# Rear_Lamp.net
KiCad netlist of a schematic drawn in EAGLE
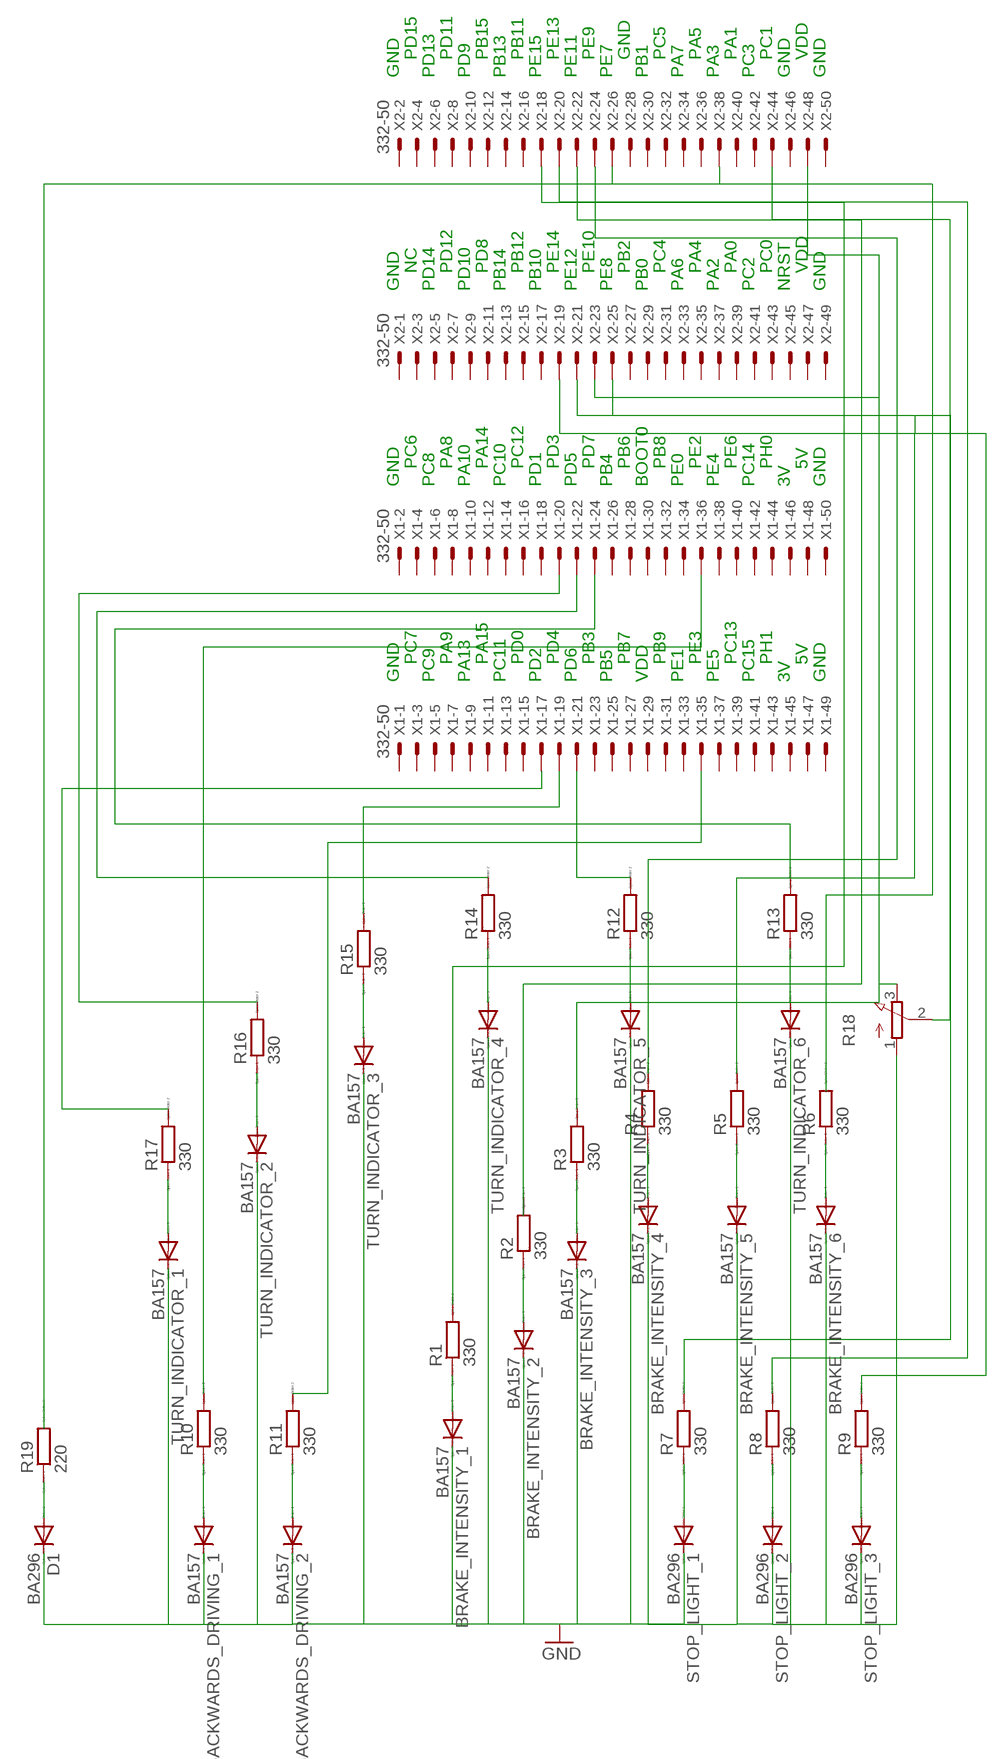
[diagram p0: schematic, sheet 1]

(export (version "E")
  (design (tool "Eeschema 10.0.6"))
  (components
    (comp (ref "BACKWARDS_DRIVING_1")
      (value "BA157")
      (footprint "eagle-import:P1-10")
      (libsource (lib "eagle-import") (part "BA157"))
    )
    (comp (ref "BACKWARDS_DRIVING_2")
      (value "BA157")
      (footprint "eagle-import:P1-10")
      (libsource (lib "eagle-import") (part "BA157"))
    )
    (comp (ref "BRAKE_INTENSITY_1")
      (value "BA157")
      (footprint "eagle-import:P1-10")
      (libsource (lib "eagle-import") (part "BA157"))
    )
    (comp (ref "BRAKE_INTENSITY_2")
      (value "BA157")
      (footprint "eagle-import:P1-10")
      (libsource (lib "eagle-import") (part "BA157"))
    )
    (comp (ref "BRAKE_INTENSITY_3")
      (value "BA157")
      (footprint "eagle-import:P1-10")
      (libsource (lib "eagle-import") (part "BA157"))
    )
    (comp (ref "BRAKE_INTENSITY_4")
      (value "BA157")
      (footprint "eagle-import:P1-10")
      (libsource (lib "eagle-import") (part "BA157"))
    )
    (comp (ref "BRAKE_INTENSITY_5")
      (value "BA157")
      (footprint "eagle-import:P1-10")
      (libsource (lib "eagle-import") (part "BA157"))
    )
    (comp (ref "BRAKE_INTENSITY_6")
      (value "BA157")
      (footprint "eagle-import:P1-10")
      (libsource (lib "eagle-import") (part "BA157"))
    )
    (comp (ref "D1")
      (value "BA296")
      (footprint "eagle-import:P2-15")
      (libsource (lib "eagle-import") (part "BA296"))
    )
    (comp (ref "R1")
      (value "330")
      (footprint "eagle-import:0204_7")
      (libsource (lib "eagle-import") (part "R0204/7"))
    )
    (comp (ref "R2")
      (value "330")
      (footprint "eagle-import:0204_7")
      (libsource (lib "eagle-import") (part "R0204/7"))
    )
    (comp (ref "R3")
      (value "330")
      (footprint "eagle-import:0204_7")
      (libsource (lib "eagle-import") (part "R0204/7"))
    )
    (comp (ref "R4")
      (value "330")
      (footprint "eagle-import:0204_7")
      (libsource (lib "eagle-import") (part "R0204/7"))
    )
    (comp (ref "R5")
      (value "330")
      (footprint "eagle-import:0204_7")
      (libsource (lib "eagle-import") (part "R0204/7"))
    )
    (comp (ref "R6")
      (value "330")
      (footprint "eagle-import:0204_7")
      (libsource (lib "eagle-import") (part "R0204/7"))
    )
    (comp (ref "R7")
      (value "330")
      (footprint "eagle-import:0204_7")
      (libsource (lib "eagle-import") (part "R0204/7"))
    )
    (comp (ref "R8")
      (value "330")
      (footprint "eagle-import:0204_7")
      (libsource (lib "eagle-import") (part "R0204/7"))
    )
    (comp (ref "R9")
      (value "330")
      (footprint "eagle-import:0204_7")
      (libsource (lib "eagle-import") (part "R0204/7"))
    )
    (comp (ref "R10")
      (value "330")
      (footprint "eagle-import:0204_7")
      (libsource (lib "eagle-import") (part "R0204/7"))
    )
    (comp (ref "R11")
      (value "330")
      (footprint "eagle-import:0204_7")
      (libsource (lib "eagle-import") (part "R0204/7"))
    )
    (comp (ref "R12")
      (value "330")
      (footprint "eagle-import:0204_7")
      (libsource (lib "eagle-import") (part "R0204/7"))
    )
    (comp (ref "R13")
      (value "330")
      (footprint "eagle-import:0204_7")
      (libsource (lib "eagle-import") (part "R0204/7"))
    )
    (comp (ref "R14")
      (value "330")
      (footprint "eagle-import:0204_7")
      (libsource (lib "eagle-import") (part "R0204/7"))
    )
    (comp (ref "R15")
      (value "330")
      (footprint "eagle-import:0204_7")
      (libsource (lib "eagle-import") (part "R0204/7"))
    )
    (comp (ref "R16")
      (value "330")
      (footprint "eagle-import:0204_7")
      (libsource (lib "eagle-import") (part "R0204/7"))
    )
    (comp (ref "R17")
      (value "330")
      (footprint "eagle-import:0204_7")
      (libsource (lib "eagle-import") (part "R0204/7"))
    )
    (comp (ref "R18")
      (value "3RP/1610N")
      (footprint "eagle-import:3RP_1610N")
      (libsource (lib "eagle-import") (part "3RP/1610N"))
    )
    (comp (ref "R19")
      (value "220")
      (footprint "eagle-import:0204_7")
      (libsource (lib "eagle-import") (part "R0204/7"))
    )
    (comp (ref "STOP_LIGHT_1")
      (value "BA296")
      (footprint "eagle-import:P2-15")
      (libsource (lib "eagle-import") (part "BA296"))
    )
    (comp (ref "STOP_LIGHT_2")
      (value "BA296")
      (footprint "eagle-import:P2-15")
      (libsource (lib "eagle-import") (part "BA296"))
    )
    (comp (ref "STOP_LIGHT_3")
      (value "BA296")
      (footprint "eagle-import:P2-15")
      (libsource (lib "eagle-import") (part "BA296"))
    )
    (comp (ref "TURN_INDICATOR_1")
      (value "BA157")
      (footprint "eagle-import:P1-10")
      (libsource (lib "eagle-import") (part "BA157"))
    )
    (comp (ref "TURN_INDICATOR_2")
      (value "BA157")
      (footprint "eagle-import:P1-10")
      (libsource (lib "eagle-import") (part "BA157"))
    )
    (comp (ref "TURN_INDICATOR_3")
      (value "BA157")
      (footprint "eagle-import:P1-10")
      (libsource (lib "eagle-import") (part "BA157"))
    )
    (comp (ref "TURN_INDICATOR_4")
      (value "BA157")
      (footprint "eagle-import:P1-10")
      (libsource (lib "eagle-import") (part "BA157"))
    )
    (comp (ref "TURN_INDICATOR_5")
      (value "BA157")
      (footprint "eagle-import:P1-10")
      (libsource (lib "eagle-import") (part "BA157"))
    )
    (comp (ref "TURN_INDICATOR_6")
      (value "BA157")
      (footprint "eagle-import:P1-10")
      (libsource (lib "eagle-import") (part "BA157"))
    )
    (comp (ref "X1")
      (value "332-50")
      (footprint "eagle-import:332-50")
      (libsource (lib "eagle-import") (part "332-50"))
    )
    (comp (ref "X2")
      (value "332-50")
      (footprint "eagle-import:332-50")
      (libsource (lib "eagle-import") (part "332-50"))
    )
  )
  (nets
    (net (code "2") (name "Net-(BACKWARDS_DRIVING_1-PadA)") (class "Default")
      (node (ref "BACKWARDS_DRIVING_1") (pin "A") (pinfunction "A_A") (pintype "passive"))
      (node (ref "R10") (pin "1") (pinfunction "1_1") (pintype "passive"))
    )
    (net (code "3") (name "Net-(BACKWARDS_DRIVING_2-PadA)") (class "Default")
      (node (ref "BACKWARDS_DRIVING_2") (pin "A") (pinfunction "A_A") (pintype "passive"))
      (node (ref "R11") (pin "1") (pinfunction "1_1") (pintype "passive"))
    )
    (net (code "4") (name "Net-(BRAKE_INTENSITY_1-PadA)") (class "Default")
      (node (ref "BRAKE_INTENSITY_1") (pin "A") (pinfunction "A_A") (pintype "passive"))
      (node (ref "R1") (pin "1") (pinfunction "1_1") (pintype "passive"))
    )
    (net (code "5") (name "Net-(BRAKE_INTENSITY_2-PadA)") (class "Default")
      (node (ref "BRAKE_INTENSITY_2") (pin "A") (pinfunction "A_A") (pintype "passive"))
      (node (ref "R2") (pin "1") (pinfunction "1_1") (pintype "passive"))
    )
    (net (code "6") (name "Net-(BRAKE_INTENSITY_3-PadA)") (class "Default")
      (node (ref "BRAKE_INTENSITY_3") (pin "A") (pinfunction "A_A") (pintype "passive"))
      (node (ref "R3") (pin "1") (pinfunction "1_1") (pintype "passive"))
    )
    (net (code "7") (name "Net-(BRAKE_INTENSITY_4-PadA)") (class "Default")
      (node (ref "BRAKE_INTENSITY_4") (pin "A") (pinfunction "A_A") (pintype "passive"))
      (node (ref "R4") (pin "1") (pinfunction "1_1") (pintype "passive"))
    )
    (net (code "8") (name "Net-(BRAKE_INTENSITY_5-PadA)") (class "Default")
      (node (ref "BRAKE_INTENSITY_5") (pin "A") (pinfunction "A_A") (pintype "passive"))
      (node (ref "R5") (pin "1") (pinfunction "1_1") (pintype "passive"))
    )
    (net (code "9") (name "Net-(BRAKE_INTENSITY_6-PadA)") (class "Default")
      (node (ref "BRAKE_INTENSITY_6") (pin "A") (pinfunction "A_A") (pintype "passive"))
      (node (ref "R6") (pin "1") (pinfunction "1_1") (pintype "passive"))
    )
    (net (code "10") (name "Net-(D1-PadA)") (class "Default")
      (node (ref "D1") (pin "A") (pinfunction "A_A") (pintype "passive"))
      (node (ref "R19") (pin "1") (pinfunction "1_1") (pintype "passive"))
    )
    (net (code "11") (name "Net-(R7-Pad1)") (class "Default")
      (node (ref "R7") (pin "1") (pinfunction "1_1") (pintype "passive"))
      (node (ref "STOP_LIGHT_1") (pin "A") (pinfunction "A_A") (pintype "passive"))
    )
    (net (code "12") (name "Net-(R8-Pad1)") (class "Default")
      (node (ref "R8") (pin "1") (pinfunction "1_1") (pintype "passive"))
      (node (ref "STOP_LIGHT_2") (pin "A") (pinfunction "A_A") (pintype "passive"))
    )
    (net (code "13") (name "Net-(R9-Pad1)") (class "Default")
      (node (ref "R9") (pin "1") (pinfunction "1_1") (pintype "passive"))
      (node (ref "STOP_LIGHT_3") (pin "A") (pinfunction "A_A") (pintype "passive"))
    )
    (net (code "14") (name "Net-(R12-Pad1)") (class "Default")
      (node (ref "R12") (pin "1") (pinfunction "1_1") (pintype "passive"))
      (node (ref "TURN_INDICATOR_5") (pin "A") (pinfunction "A_A") (pintype "passive"))
    )
    (net (code "15") (name "Net-(R13-Pad1)") (class "Default")
      (node (ref "R13") (pin "1") (pinfunction "1_1") (pintype "passive"))
      (node (ref "TURN_INDICATOR_6") (pin "A") (pinfunction "A_A") (pintype "passive"))
    )
    (net (code "16") (name "Net-(R14-Pad1)") (class "Default")
      (node (ref "R14") (pin "1") (pinfunction "1_1") (pintype "passive"))
      (node (ref "TURN_INDICATOR_4") (pin "A") (pinfunction "A_A") (pintype "passive"))
    )
    (net (code "17") (name "Net-(R15-Pad1)") (class "Default")
      (node (ref "R15") (pin "1") (pinfunction "1_1") (pintype "passive"))
      (node (ref "TURN_INDICATOR_3") (pin "A") (pinfunction "A_A") (pintype "passive"))
    )
    (net (code "18") (name "Net-(R16-Pad1)") (class "Default")
      (node (ref "R16") (pin "1") (pinfunction "1_1") (pintype "passive"))
      (node (ref "TURN_INDICATOR_2") (pin "A") (pinfunction "A_A") (pintype "passive"))
    )
    (net (code "19") (name "Net-(R17-Pad1)") (class "Default")
      (node (ref "R17") (pin "1") (pinfunction "1_1") (pintype "passive"))
      (node (ref "TURN_INDICATOR_1") (pin "A") (pinfunction "A_A") (pintype "passive"))
    )
    (net (code "20") (name "Net-(R18-A)") (class "Default")
      (node (ref "BACKWARDS_DRIVING_1") (pin "C") (pinfunction "C_C") (pintype "passive"))
      (node (ref "BACKWARDS_DRIVING_2") (pin "C") (pinfunction "C_C") (pintype "passive"))
      (node (ref "BRAKE_INTENSITY_1") (pin "C") (pinfunction "C_C") (pintype "passive"))
      (node (ref "BRAKE_INTENSITY_2") (pin "C") (pinfunction "C_C") (pintype "passive"))
      (node (ref "BRAKE_INTENSITY_3") (pin "C") (pinfunction "C_C") (pintype "passive"))
      (node (ref "BRAKE_INTENSITY_4") (pin "C") (pinfunction "C_C") (pintype "passive"))
      (node (ref "BRAKE_INTENSITY_5") (pin "C") (pinfunction "C_C") (pintype "passive"))
      (node (ref "BRAKE_INTENSITY_6") (pin "C") (pinfunction "C_C") (pintype "passive"))
      (node (ref "D1") (pin "C") (pinfunction "C_C") (pintype "passive"))
      (node (ref "R18") (pin "1") (pinfunction "A_1") (pintype "passive"))
      (node (ref "STOP_LIGHT_1") (pin "C") (pinfunction "C_C") (pintype "passive"))
      (node (ref "STOP_LIGHT_2") (pin "C") (pinfunction "C_C") (pintype "passive"))
      (node (ref "STOP_LIGHT_3") (pin "C") (pinfunction "C_C") (pintype "passive"))
      (node (ref "TURN_INDICATOR_1") (pin "C") (pinfunction "C_C") (pintype "passive"))
      (node (ref "TURN_INDICATOR_2") (pin "C") (pinfunction "C_C") (pintype "passive"))
      (node (ref "TURN_INDICATOR_3") (pin "C") (pinfunction "C_C") (pintype "passive"))
      (node (ref "TURN_INDICATOR_4") (pin "C") (pinfunction "C_C") (pintype "passive"))
      (node (ref "TURN_INDICATOR_5") (pin "C") (pinfunction "C_C") (pintype "passive"))
      (node (ref "TURN_INDICATOR_6") (pin "C") (pinfunction "C_C") (pintype "passive"))
    )
    (net (code "21") (name "Net-(R18-E)") (class "Default")
      (node (ref "R18") (pin "3") (pinfunction "E_3") (pintype "passive"))
      (node (ref "X2") (pin "48") (pinfunction "S_48") (pintype "passive"))
    )
    (net (code "22") (name "Net-(R18-S)") (class "Default")
      (node (ref "R18") (pin "2") (pinfunction "S_2") (pintype "passive"))
      (node (ref "X2") (pin "44") (pinfunction "S_44") (pintype "passive"))
    )
    (net (code "23") (name "Net-(X1AC-S)") (class "Default")
      (node (ref "R11") (pin "2") (pinfunction "2_2") (pintype "passive"))
      (node (ref "X1") (pin "35") (pinfunction "S_35") (pintype "passive"))
    )
    (net (code "24") (name "Net-(X1AD-S)") (class "Default")
      (node (ref "R10") (pin "2") (pinfunction "2_2") (pintype "passive"))
      (node (ref "X1") (pin "36") (pinfunction "S_36") (pintype "passive"))
    )
    (net (code "25") (name "Net-(X1I-S)") (class "Default")
      (node (ref "R17") (pin "2") (pinfunction "2_2") (pintype "passive"))
      (node (ref "X1") (pin "17") (pinfunction "S_17") (pintype "passive"))
    )
    (net (code "26") (name "Net-(X1K-S)") (class "Default")
      (node (ref "R15") (pin "2") (pinfunction "2_2") (pintype "passive"))
      (node (ref "X1") (pin "19") (pinfunction "S_19") (pintype "passive"))
    )
    (net (code "27") (name "Net-(X1M-S)") (class "Default")
      (node (ref "R16") (pin "2") (pinfunction "2_2") (pintype "passive"))
      (node (ref "X1") (pin "20") (pinfunction "S_20") (pintype "passive"))
    )
    (net (code "28") (name "Net-(X1N-S)") (class "Default")
      (node (ref "R12") (pin "2") (pinfunction "2_2") (pintype "passive"))
      (node (ref "X1") (pin "21") (pinfunction "S_21") (pintype "passive"))
    )
    (net (code "29") (name "Net-(X1O-S)") (class "Default")
      (node (ref "R14") (pin "2") (pinfunction "2_2") (pintype "passive"))
      (node (ref "X1") (pin "22") (pinfunction "S_22") (pintype "passive"))
    )
    (net (code "30") (name "Net-(X1Q-S)") (class "Default")
      (node (ref "R13") (pin "2") (pinfunction "2_2") (pintype "passive"))
      (node (ref "X1") (pin "24") (pinfunction "S_24") (pintype "passive"))
    )
    (net (code "31") (name "Net-(X2J-S)") (class "Default")
      (node (ref "R1") (pin "2") (pinfunction "2_2") (pintype "passive"))
      (node (ref "X2") (pin "18") (pinfunction "S_18") (pintype "passive"))
    )
    (net (code "32") (name "Net-(X2K-S)") (class "Default")
      (node (ref "R9") (pin "2") (pinfunction "2_2") (pintype "passive"))
      (node (ref "X2") (pin "19") (pinfunction "S_19") (pintype "passive"))
    )
    (net (code "33") (name "Net-(X2M-S)") (class "Default")
      (node (ref "R8") (pin "2") (pinfunction "2_2") (pintype "passive"))
      (node (ref "X2") (pin "20") (pinfunction "S_20") (pintype "passive"))
    )
    (net (code "34") (name "Net-(X2N-S)") (class "Default")
      (node (ref "R7") (pin "2") (pinfunction "2_2") (pintype "passive"))
      (node (ref "X2") (pin "21") (pinfunction "S_21") (pintype "passive"))
    )
    (net (code "35") (name "Net-(X2P-S)") (class "Default")
      (node (ref "R3") (pin "2") (pinfunction "2_2") (pintype "passive"))
      (node (ref "X2") (pin "23") (pinfunction "S_23") (pintype "passive"))
    )
    (net (code "36") (name "Net-(X2Q-S)") (class "Default")
      (node (ref "R4") (pin "2") (pinfunction "2_2") (pintype "passive"))
      (node (ref "X2") (pin "24") (pinfunction "S_24") (pintype "passive"))
    )
    (net (code "37") (name "Net-(X2R-S)") (class "Default")
      (node (ref "R5") (pin "2") (pinfunction "2_2") (pintype "passive"))
      (node (ref "X2") (pin "25") (pinfunction "S_25") (pintype "passive"))
    )
    (net (code "38") (name "unconnected-(R2-Pad2)") (class "Default")
      (node (ref "R2") (pin "2") (pinfunction "2_2") (pintype "passive"))
    )
    (net (code "39") (name "unconnected-(R6-Pad2)") (class "Default")
      (node (ref "R6") (pin "2") (pinfunction "2_2") (pintype "passive"))
    )
    (net (code "40") (name "unconnected-(R19-Pad2)") (class "Default")
      (node (ref "R19") (pin "2") (pinfunction "2_2") (pintype "passive"))
    )
    (net (code "41") (name "unconnected-(X1A-S-Pad1)") (class "Default")
      (node (ref "X1") (pin "1") (pinfunction "S_1") (pintype "passive"))
    )
    (net (code "42") (name "unconnected-(X1AA-S-Pad33)") (class "Default")
      (node (ref "X1") (pin "33") (pinfunction "S_33") (pintype "passive"))
    )
    (net (code "43") (name "unconnected-(X1AB-S-Pad34)") (class "Default")
      (node (ref "X1") (pin "34") (pinfunction "S_34") (pintype "passive"))
    )
    (net (code "44") (name "unconnected-(X1AE-S-Pad37)") (class "Default")
      (node (ref "X1") (pin "37") (pinfunction "S_37") (pintype "passive"))
    )
    (net (code "45") (name "unconnected-(X1AF-S-Pad38)") (class "Default")
      (node (ref "X1") (pin "38") (pinfunction "S_38") (pintype "passive"))
    )
    (net (code "46") (name "unconnected-(X1AG-S-Pad39)") (class "Default")
      (node (ref "X1") (pin "39") (pinfunction "S_39") (pintype "passive"))
    )
    (net (code "47") (name "unconnected-(X1AH-S-Pad4)") (class "Default")
      (node (ref "X1") (pin "4") (pinfunction "S_4") (pintype "passive"))
    )
    (net (code "48") (name "unconnected-(X1AI-S-Pad40)") (class "Default")
      (node (ref "X1") (pin "40") (pinfunction "S_40") (pintype "passive"))
    )
    (net (code "49") (name "unconnected-(X1AJ-S-Pad41)") (class "Default")
      (node (ref "X1") (pin "41") (pinfunction "S_41") (pintype "passive"))
    )
    (net (code "50") (name "unconnected-(X1AK-S-Pad42)") (class "Default")
      (node (ref "X1") (pin "42") (pinfunction "S_42") (pintype "passive"))
    )
    (net (code "51") (name "unconnected-(X1AL-S-Pad43)") (class "Default")
      (node (ref "X1") (pin "43") (pinfunction "S_43") (pintype "passive"))
    )
    (net (code "52") (name "unconnected-(X1AM-S-Pad44)") (class "Default")
      (node (ref "X1") (pin "44") (pinfunction "S_44") (pintype "passive"))
    )
    (net (code "53") (name "unconnected-(X1AN-S-Pad45)") (class "Default")
      (node (ref "X1") (pin "45") (pinfunction "S_45") (pintype "passive"))
    )
    (net (code "54") (name "unconnected-(X1AO-S-Pad46)") (class "Default")
      (node (ref "X1") (pin "46") (pinfunction "S_46") (pintype "passive"))
    )
    (net (code "55") (name "unconnected-(X1AP-S-Pad47)") (class "Default")
      (node (ref "X1") (pin "47") (pinfunction "S_47") (pintype "passive"))
    )
    (net (code "56") (name "unconnected-(X1AQ-S-Pad48)") (class "Default")
      (node (ref "X1") (pin "48") (pinfunction "S_48") (pintype "passive"))
    )
    (net (code "57") (name "unconnected-(X1AR-S-Pad49)") (class "Default")
      (node (ref "X1") (pin "49") (pinfunction "S_49") (pintype "passive"))
    )
    (net (code "58") (name "unconnected-(X1AS-S-Pad5)") (class "Default")
      (node (ref "X1") (pin "5") (pinfunction "S_5") (pintype "passive"))
    )
    (net (code "59") (name "unconnected-(X1AT-S-Pad50)") (class "Default")
      (node (ref "X1") (pin "50") (pinfunction "S_50") (pintype "passive"))
    )
    (net (code "60") (name "unconnected-(X1AU-S-Pad6)") (class "Default")
      (node (ref "X1") (pin "6") (pinfunction "S_6") (pintype "passive"))
    )
    (net (code "61") (name "unconnected-(X1AV-S-Pad7)") (class "Default")
      (node (ref "X1") (pin "7") (pinfunction "S_7") (pintype "passive"))
    )
    (net (code "62") (name "unconnected-(X1AW-S-Pad8)") (class "Default")
      (node (ref "X1") (pin "8") (pinfunction "S_8") (pintype "passive"))
    )
    (net (code "63") (name "unconnected-(X1AX-S-Pad9)") (class "Default")
      (node (ref "X1") (pin "9") (pinfunction "S_9") (pintype "passive"))
    )
    (net (code "64") (name "unconnected-(X1B-S-Pad10)") (class "Default")
      (node (ref "X1") (pin "10") (pinfunction "S_10") (pintype "passive"))
    )
    (net (code "65") (name "unconnected-(X1C-S-Pad11)") (class "Default")
      (node (ref "X1") (pin "11") (pinfunction "S_11") (pintype "passive"))
    )
    (net (code "66") (name "unconnected-(X1D-S-Pad12)") (class "Default")
      (node (ref "X1") (pin "12") (pinfunction "S_12") (pintype "passive"))
    )
    (net (code "67") (name "unconnected-(X1E-S-Pad13)") (class "Default")
      (node (ref "X1") (pin "13") (pinfunction "S_13") (pintype "passive"))
    )
    (net (code "68") (name "unconnected-(X1F-S-Pad14)") (class "Default")
      (node (ref "X1") (pin "14") (pinfunction "S_14") (pintype "passive"))
    )
    (net (code "69") (name "unconnected-(X1G-S-Pad15)") (class "Default")
      (node (ref "X1") (pin "15") (pinfunction "S_15") (pintype "passive"))
    )
    (net (code "70") (name "unconnected-(X1H-S-Pad16)") (class "Default")
      (node (ref "X1") (pin "16") (pinfunction "S_16") (pintype "passive"))
    )
    (net (code "71") (name "unconnected-(X1J-S-Pad18)") (class "Default")
      (node (ref "X1") (pin "18") (pinfunction "S_18") (pintype "passive"))
    )
    (net (code "72") (name "unconnected-(X1L-S-Pad2)") (class "Default")
      (node (ref "X1") (pin "2") (pinfunction "S_2") (pintype "passive"))
    )
    (net (code "73") (name "unconnected-(X1P-S-Pad23)") (class "Default")
      (node (ref "X1") (pin "23") (pinfunction "S_23") (pintype "passive"))
    )
    (net (code "74") (name "unconnected-(X1R-S-Pad25)") (class "Default")
      (node (ref "X1") (pin "25") (pinfunction "S_25") (pintype "passive"))
    )
    (net (code "75") (name "unconnected-(X1S-S-Pad26)") (class "Default")
      (node (ref "X1") (pin "26") (pinfunction "S_26") (pintype "passive"))
    )
    (net (code "76") (name "unconnected-(X1T-S-Pad27)") (class "Default")
      (node (ref "X1") (pin "27") (pinfunction "S_27") (pintype "passive"))
    )
    (net (code "77") (name "unconnected-(X1U-S-Pad28)") (class "Default")
      (node (ref "X1") (pin "28") (pinfunction "S_28") (pintype "passive"))
    )
    (net (code "78") (name "unconnected-(X1V-S-Pad29)") (class "Default")
      (node (ref "X1") (pin "29") (pinfunction "S_29") (pintype "passive"))
    )
    (net (code "79") (name "unconnected-(X1W-S-Pad3)") (class "Default")
      (node (ref "X1") (pin "3") (pinfunction "S_3") (pintype "passive"))
    )
    (net (code "80") (name "unconnected-(X1X-S-Pad30)") (class "Default")
      (node (ref "X1") (pin "30") (pinfunction "S_30") (pintype "passive"))
    )
    (net (code "81") (name "unconnected-(X1Y-S-Pad31)") (class "Default")
      (node (ref "X1") (pin "31") (pinfunction "S_31") (pintype "passive"))
    )
    (net (code "82") (name "unconnected-(X1Z-S-Pad32)") (class "Default")
      (node (ref "X1") (pin "32") (pinfunction "S_32") (pintype "passive"))
    )
    (net (code "83") (name "unconnected-(X2A-S-Pad1)") (class "Default")
      (node (ref "X2") (pin "1") (pinfunction "S_1") (pintype "passive"))
    )
    (net (code "84") (name "unconnected-(X2AA-S-Pad33)") (class "Default")
      (node (ref "X2") (pin "33") (pinfunction "S_33") (pintype "passive"))
    )
    (net (code "85") (name "unconnected-(X2AB-S-Pad34)") (class "Default")
      (node (ref "X2") (pin "34") (pinfunction "S_34") (pintype "passive"))
    )
    (net (code "86") (name "unconnected-(X2AC-S-Pad35)") (class "Default")
      (node (ref "X2") (pin "35") (pinfunction "S_35") (pintype "passive"))
    )
    (net (code "87") (name "unconnected-(X2AD-S-Pad36)") (class "Default")
      (node (ref "X2") (pin "36") (pinfunction "S_36") (pintype "passive"))
    )
    (net (code "88") (name "unconnected-(X2AE-S-Pad37)") (class "Default")
      (node (ref "X2") (pin "37") (pinfunction "S_37") (pintype "passive"))
    )
    (net (code "89") (name "unconnected-(X2AF-S-Pad38)") (class "Default")
      (node (ref "X2") (pin "38") (pinfunction "S_38") (pintype "passive"))
    )
    (net (code "90") (name "unconnected-(X2AG-S-Pad39)") (class "Default")
      (node (ref "X2") (pin "39") (pinfunction "S_39") (pintype "passive"))
    )
    (net (code "91") (name "unconnected-(X2AH-S-Pad4)") (class "Default")
      (node (ref "X2") (pin "4") (pinfunction "S_4") (pintype "passive"))
    )
    (net (code "92") (name "unconnected-(X2AI-S-Pad40)") (class "Default")
      (node (ref "X2") (pin "40") (pinfunction "S_40") (pintype "passive"))
    )
    (net (code "93") (name "unconnected-(X2AJ-S-Pad41)") (class "Default")
      (node (ref "X2") (pin "41") (pinfunction "S_41") (pintype "passive"))
    )
    (net (code "94") (name "unconnected-(X2AK-S-Pad42)") (class "Default")
      (node (ref "X2") (pin "42") (pinfunction "S_42") (pintype "passive"))
    )
    (net (code "95") (name "unconnected-(X2AL-S-Pad43)") (class "Default")
      (node (ref "X2") (pin "43") (pinfunction "S_43") (pintype "passive"))
    )
    (net (code "96") (name "unconnected-(X2AN-S-Pad45)") (class "Default")
      (node (ref "X2") (pin "45") (pinfunction "S_45") (pintype "passive"))
    )
    (net (code "97") (name "unconnected-(X2AO-S-Pad46)") (class "Default")
      (node (ref "X2") (pin "46") (pinfunction "S_46") (pintype "passive"))
    )
    (net (code "98") (name "unconnected-(X2AP-S-Pad47)") (class "Default")
      (node (ref "X2") (pin "47") (pinfunction "S_47") (pintype "passive"))
    )
    (net (code "99") (name "unconnected-(X2AR-S-Pad49)") (class "Default")
      (node (ref "X2") (pin "49") (pinfunction "S_49") (pintype "passive"))
    )
    (net (code "100") (name "unconnected-(X2AS-S-Pad5)") (class "Default")
      (node (ref "X2") (pin "5") (pinfunction "S_5") (pintype "passive"))
    )
    (net (code "101") (name "unconnected-(X2AT-S-Pad50)") (class "Default")
      (node (ref "X2") (pin "50") (pinfunction "S_50") (pintype "passive"))
    )
    (net (code "102") (name "unconnected-(X2AU-S-Pad6)") (class "Default")
      (node (ref "X2") (pin "6") (pinfunction "S_6") (pintype "passive"))
    )
    (net (code "103") (name "unconnected-(X2AV-S-Pad7)") (class "Default")
      (node (ref "X2") (pin "7") (pinfunction "S_7") (pintype "passive"))
    )
    (net (code "104") (name "unconnected-(X2AW-S-Pad8)") (class "Default")
      (node (ref "X2") (pin "8") (pinfunction "S_8") (pintype "passive"))
    )
    (net (code "105") (name "unconnected-(X2AX-S-Pad9)") (class "Default")
      (node (ref "X2") (pin "9") (pinfunction "S_9") (pintype "passive"))
    )
    (net (code "106") (name "unconnected-(X2B-S-Pad10)") (class "Default")
      (node (ref "X2") (pin "10") (pinfunction "S_10") (pintype "passive"))
    )
    (net (code "107") (name "unconnected-(X2C-S-Pad11)") (class "Default")
      (node (ref "X2") (pin "11") (pinfunction "S_11") (pintype "passive"))
    )
    (net (code "108") (name "unconnected-(X2D-S-Pad12)") (class "Default")
      (node (ref "X2") (pin "12") (pinfunction "S_12") (pintype "passive"))
    )
    (net (code "109") (name "unconnected-(X2E-S-Pad13)") (class "Default")
      (node (ref "X2") (pin "13") (pinfunction "S_13") (pintype "passive"))
    )
    (net (code "110") (name "unconnected-(X2F-S-Pad14)") (class "Default")
      (node (ref "X2") (pin "14") (pinfunction "S_14") (pintype "passive"))
    )
    (net (code "111") (name "unconnected-(X2G-S-Pad15)") (class "Default")
      (node (ref "X2") (pin "15") (pinfunction "S_15") (pintype "passive"))
    )
    (net (code "112") (name "unconnected-(X2H-S-Pad16)") (class "Default")
      (node (ref "X2") (pin "16") (pinfunction "S_16") (pintype "passive"))
    )
    (net (code "113") (name "unconnected-(X2I-S-Pad17)") (class "Default")
      (node (ref "X2") (pin "17") (pinfunction "S_17") (pintype "passive"))
    )
    (net (code "114") (name "unconnected-(X2L-S-Pad2)") (class "Default")
      (node (ref "X2") (pin "2") (pinfunction "S_2") (pintype "passive"))
    )
    (net (code "115") (name "unconnected-(X2O-S-Pad22)") (class "Default")
      (node (ref "X2") (pin "22") (pinfunction "S_22") (pintype "passive"))
    )
    (net (code "116") (name "unconnected-(X2S-S-Pad26)") (class "Default")
      (node (ref "X2") (pin "26") (pinfunction "S_26") (pintype "passive"))
    )
    (net (code "117") (name "unconnected-(X2T-S-Pad27)") (class "Default")
      (node (ref "X2") (pin "27") (pinfunction "S_27") (pintype "passive"))
    )
    (net (code "118") (name "unconnected-(X2U-S-Pad28)") (class "Default")
      (node (ref "X2") (pin "28") (pinfunction "S_28") (pintype "passive"))
    )
    (net (code "119") (name "unconnected-(X2V-S-Pad29)") (class "Default")
      (node (ref "X2") (pin "29") (pinfunction "S_29") (pintype "passive"))
    )
    (net (code "120") (name "unconnected-(X2W-S-Pad3)") (class "Default")
      (node (ref "X2") (pin "3") (pinfunction "S_3") (pintype "passive"))
    )
    (net (code "121") (name "unconnected-(X2X-S-Pad30)") (class "Default")
      (node (ref "X2") (pin "30") (pinfunction "S_30") (pintype "passive"))
    )
    (net (code "122") (name "unconnected-(X2Y-S-Pad31)") (class "Default")
      (node (ref "X2") (pin "31") (pinfunction "S_31") (pintype "passive"))
    )
    (net (code "123") (name "unconnected-(X2Z-S-Pad32)") (class "Default")
      (node (ref "X2") (pin "32") (pinfunction "S_32") (pintype "passive"))
    )
  )
)
